# 7-channel-PWM_compact.net
KiCad netlist of a schematic drawn in EAGLE
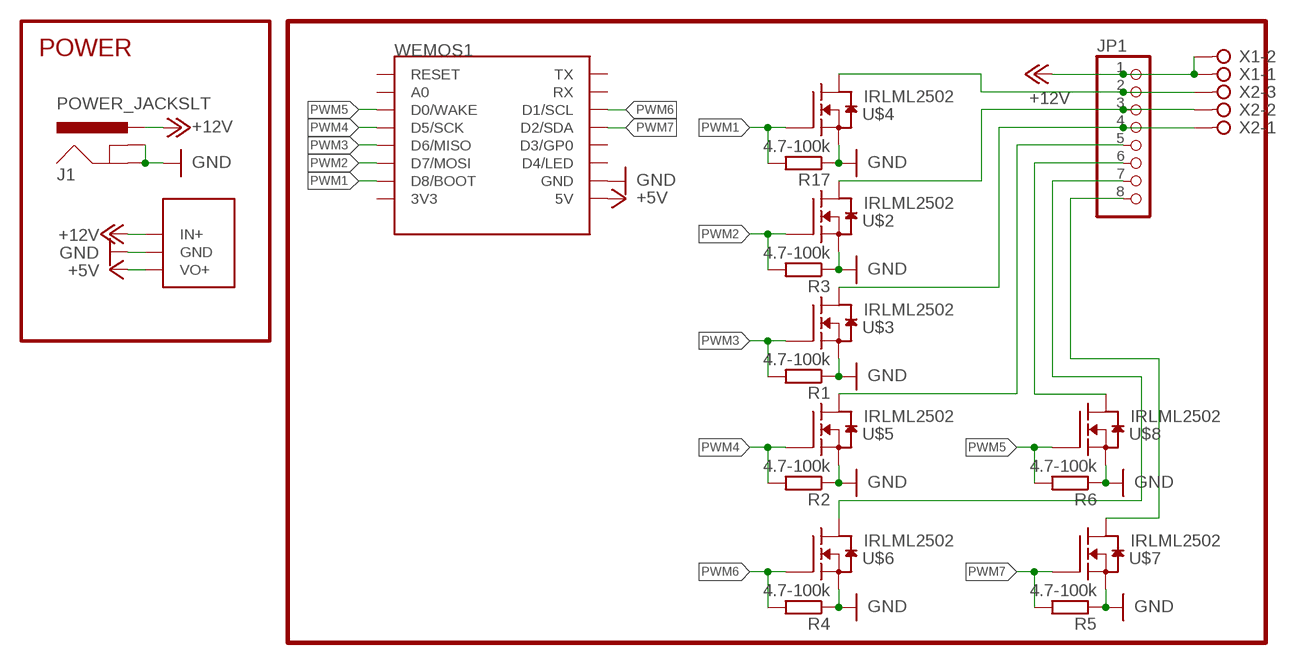
[diagram p0: schematic, sheet 1]

(export (version "E")
  (design (tool "Eeschema 10.0.6"))
  (components
    (comp (ref "J1")
      (value "POWER_JACKSLT")
      (footprint "eagle-import:POWER_JACK_SLOT")
      (libsource (lib "eagle-import") (part "POWER_JACKSLT"))
    )
    (comp (ref "JP1")
      (value "PINHD-1X08_2.54-S")
      (footprint "eagle-import:1X08-S")
      (libsource (lib "eagle-import") (part "PINHD-1X08_2.54-S"))
    )
    (comp (ref "R1")
      (value "4.7-100k")
      (footprint "eagle-import:R0805")
      (libsource (lib "eagle-import") (part "R-EU_R0805"))
    )
    (comp (ref "R2")
      (value "4.7-100k")
      (footprint "eagle-import:R0805")
      (libsource (lib "eagle-import") (part "R-EU_R0805"))
    )
    (comp (ref "R3")
      (value "4.7-100k")
      (footprint "eagle-import:R0805")
      (libsource (lib "eagle-import") (part "R-EU_R0805"))
    )
    (comp (ref "R4")
      (value "4.7-100k")
      (footprint "eagle-import:R0805")
      (libsource (lib "eagle-import") (part "R-EU_R0805"))
    )
    (comp (ref "R5")
      (value "4.7-100k")
      (footprint "eagle-import:R0805")
      (libsource (lib "eagle-import") (part "R-EU_R0805"))
    )
    (comp (ref "R6")
      (value "4.7-100k")
      (footprint "eagle-import:R0805")
      (libsource (lib "eagle-import") (part "R-EU_R0805"))
    )
    (comp (ref "R17")
      (value "4.7-100k")
      (footprint "eagle-import:R0805")
      (libsource (lib "eagle-import") (part "R-EU_R0805"))
    )
    (comp (ref "U$1")
      (value "BUCK_CONVERTER_TE818_VAR")
      (footprint "eagle-import:BUCK_CONVERTER_TE818_VAR")
      (libsource (lib "eagle-import") (part "BUCK_CONVERTER_TE818_VAR"))
    )
    (comp (ref "U$2")
      (value "IRLML2502")
      (footprint "eagle-import:SOT23")
      (libsource (lib "eagle-import") (part "N-CH_IRLML2502"))
    )
    (comp (ref "U$3")
      (value "IRLML2502")
      (footprint "eagle-import:SOT23")
      (libsource (lib "eagle-import") (part "N-CH_IRLML2502"))
    )
    (comp (ref "U$4")
      (value "IRLML2502")
      (footprint "eagle-import:SOT23")
      (libsource (lib "eagle-import") (part "N-CH_IRLML2502"))
    )
    (comp (ref "U$5")
      (value "IRLML2502")
      (footprint "eagle-import:SOT23")
      (libsource (lib "eagle-import") (part "N-CH_IRLML2502"))
    )
    (comp (ref "U$6")
      (value "IRLML2502")
      (footprint "eagle-import:SOT23")
      (libsource (lib "eagle-import") (part "N-CH_IRLML2502"))
    )
    (comp (ref "U$7")
      (value "IRLML2502")
      (footprint "eagle-import:SOT23")
      (libsource (lib "eagle-import") (part "N-CH_IRLML2502"))
    )
    (comp (ref "U$8")
      (value "IRLML2502")
      (footprint "eagle-import:SOT23")
      (libsource (lib "eagle-import") (part "N-CH_IRLML2502"))
    )
    (comp (ref "WEMOS1")
      (value "WEMOS-D1-MINI")
      (footprint "eagle-import:WEMOS-D1-MINI")
      (libsource (lib "eagle-import") (part "WEMOS-D1-MINI"))
    )
    (comp (ref "X1")
      (value "W237-02P")
      (footprint "eagle-import:W237-132")
      (libsource (lib "eagle-import") (part "W237-02P"))
    )
    (comp (ref "X2")
      (value "W237-03P")
      (footprint "eagle-import:W237-133")
      (libsource (lib "eagle-import") (part "W237-03P"))
    )
  )
  (nets
    (net (code "1") (name "+5V") (class "Default")
      (node (ref "U$1") (pin "VO+") (pinfunction "VO+_VO+") (pintype "bidirectional"))
      (node (ref "WEMOS1") (pin "5V") (pinfunction "5V_5V") (pintype "bidirectional"))
    )
    (net (code "2") (name "+12V") (class "Default")
      (node (ref "J1") (pin "PWR") (pinfunction "PWR_PWR") (pintype "bidirectional"))
      (node (ref "JP1") (pin "1") (pinfunction "1_1") (pintype "passive"))
      (node (ref "U$1") (pin "IN+") (pinfunction "IN+_IN+") (pintype "bidirectional"))
      (node (ref "X1") (pin "1") (pinfunction "KL_1") (pintype "passive"))
      (node (ref "X1") (pin "2") (pinfunction "KL_2") (pintype "passive"))
    )
    (net (code "3") (name "GND") (class "Default")
      (node (ref "J1") (pin "GND@1") (pinfunction "GNDBREAK_GND@1") (pintype "bidirectional"))
      (node (ref "J1") (pin "GND@2") (pinfunction "GND_GND@2") (pintype "bidirectional"))
      (node (ref "R1") (pin "1") (pinfunction "1_1") (pintype "passive"))
      (node (ref "R17") (pin "1") (pinfunction "1_1") (pintype "passive"))
      (node (ref "R2") (pin "1") (pinfunction "1_1") (pintype "passive"))
      (node (ref "R3") (pin "1") (pinfunction "1_1") (pintype "passive"))
      (node (ref "R4") (pin "1") (pinfunction "1_1") (pintype "passive"))
      (node (ref "R5") (pin "1") (pinfunction "1_1") (pintype "passive"))
      (node (ref "R6") (pin "1") (pinfunction "1_1") (pintype "passive"))
      (node (ref "U$1") (pin "GND") (pinfunction "GND_GND") (pintype "bidirectional"))
      (node (ref "U$2") (pin "2") (pinfunction "S_2") (pintype "passive"))
      (node (ref "U$3") (pin "2") (pinfunction "S_2") (pintype "passive"))
      (node (ref "U$4") (pin "2") (pinfunction "S_2") (pintype "passive"))
      (node (ref "U$5") (pin "2") (pinfunction "S_2") (pintype "passive"))
      (node (ref "U$6") (pin "2") (pinfunction "S_2") (pintype "passive"))
      (node (ref "U$7") (pin "2") (pinfunction "S_2") (pintype "passive"))
      (node (ref "U$8") (pin "2") (pinfunction "S_2") (pintype "passive"))
      (node (ref "WEMOS1") (pin "GND") (pinfunction "GND_GND") (pintype "bidirectional"))
    )
    (net (code "4") (name "Net-(U$2-D)") (class "Default")
      (node (ref "JP1") (pin "3") (pinfunction "3_3") (pintype "passive"))
      (node (ref "U$2") (pin "3") (pinfunction "D_3") (pintype "passive"))
      (node (ref "X2") (pin "2") (pinfunction "KL_2") (pintype "passive"))
    )
    (net (code "5") (name "Net-(U$3-D)") (class "Default")
      (node (ref "JP1") (pin "4") (pinfunction "4_4") (pintype "passive"))
      (node (ref "U$3") (pin "3") (pinfunction "D_3") (pintype "passive"))
      (node (ref "X2") (pin "1") (pinfunction "KL_1") (pintype "passive"))
    )
    (net (code "6") (name "Net-(U$4-D)") (class "Default")
      (node (ref "JP1") (pin "2") (pinfunction "2_2") (pintype "passive"))
      (node (ref "U$4") (pin "3") (pinfunction "D_3") (pintype "passive"))
      (node (ref "X2") (pin "3") (pinfunction "KL_3") (pintype "passive"))
    )
    (net (code "7") (name "Net-(U$5-D)") (class "Default")
      (node (ref "JP1") (pin "5") (pinfunction "5_5") (pintype "passive"))
      (node (ref "U$5") (pin "3") (pinfunction "D_3") (pintype "passive"))
    )
    (net (code "8") (name "Net-(U$6-D)") (class "Default")
      (node (ref "JP1") (pin "7") (pinfunction "7_7") (pintype "passive"))
      (node (ref "U$6") (pin "3") (pinfunction "D_3") (pintype "passive"))
    )
    (net (code "9") (name "Net-(U$7-D)") (class "Default")
      (node (ref "JP1") (pin "8") (pinfunction "8_8") (pintype "passive"))
      (node (ref "U$7") (pin "3") (pinfunction "D_3") (pintype "passive"))
    )
    (net (code "10") (name "Net-(U$8-D)") (class "Default")
      (node (ref "JP1") (pin "6") (pinfunction "6_6") (pintype "passive"))
      (node (ref "U$8") (pin "3") (pinfunction "D_3") (pintype "passive"))
    )
    (net (code "11") (name "PWM1") (class "Default")
      (node (ref "R17") (pin "2") (pinfunction "2_2") (pintype "passive"))
      (node (ref "U$4") (pin "1") (pinfunction "G_1") (pintype "passive"))
      (node (ref "WEMOS1") (pin "D8") (pinfunction "D8/BOOT_D8") (pintype "bidirectional"))
    )
    (net (code "12") (name "PWM2") (class "Default")
      (node (ref "R3") (pin "2") (pinfunction "2_2") (pintype "passive"))
      (node (ref "U$2") (pin "1") (pinfunction "G_1") (pintype "passive"))
      (node (ref "WEMOS1") (pin "D7") (pinfunction "D7/MOSI_D7") (pintype "bidirectional"))
    )
    (net (code "13") (name "PWM3") (class "Default")
      (node (ref "R1") (pin "2") (pinfunction "2_2") (pintype "passive"))
      (node (ref "U$3") (pin "1") (pinfunction "G_1") (pintype "passive"))
      (node (ref "WEMOS1") (pin "D6") (pinfunction "D6/MISO_D6") (pintype "bidirectional"))
    )
    (net (code "14") (name "PWM4") (class "Default")
      (node (ref "R2") (pin "2") (pinfunction "2_2") (pintype "passive"))
      (node (ref "U$5") (pin "1") (pinfunction "G_1") (pintype "passive"))
      (node (ref "WEMOS1") (pin "D5") (pinfunction "D5/SCK_D5") (pintype "bidirectional"))
    )
    (net (code "15") (name "PWM5") (class "Default")
      (node (ref "R6") (pin "2") (pinfunction "2_2") (pintype "passive"))
      (node (ref "U$8") (pin "1") (pinfunction "G_1") (pintype "passive"))
      (node (ref "WEMOS1") (pin "D0") (pinfunction "D0/WAKE_D0") (pintype "bidirectional"))
    )
    (net (code "16") (name "PWM6") (class "Default")
      (node (ref "R4") (pin "2") (pinfunction "2_2") (pintype "passive"))
      (node (ref "U$6") (pin "1") (pinfunction "G_1") (pintype "passive"))
      (node (ref "WEMOS1") (pin "D1") (pinfunction "D1/SCL_D1") (pintype "bidirectional"))
    )
    (net (code "17") (name "PWM7") (class "Default")
      (node (ref "R5") (pin "2") (pinfunction "2_2") (pintype "passive"))
      (node (ref "U$7") (pin "1") (pinfunction "G_1") (pintype "passive"))
      (node (ref "WEMOS1") (pin "D2") (pinfunction "D2/SDA_D2") (pintype "bidirectional"))
    )
    (net (code "18") (name "unconnected-(WEMOS1-D3{slash}GP0-PadD3)") (class "Default")
      (node (ref "WEMOS1") (pin "D3") (pinfunction "D3/GP0_D3") (pintype "bidirectional"))
    )
    (net (code "19") (name "unconnected-(WEMOS1-D4{slash}LED-PadD4)") (class "Default")
      (node (ref "WEMOS1") (pin "D4") (pinfunction "D4/LED_D4") (pintype "bidirectional"))
    )
    (net (code "20") (name "unconnected-(WEMOS1-Pad3V3)") (class "Default")
      (node (ref "WEMOS1") (pin "3V3") (pinfunction "3V3_3V3") (pintype "bidirectional"))
    )
    (net (code "21") (name "unconnected-(WEMOS1-PadA0)") (class "Default")
      (node (ref "WEMOS1") (pin "A0") (pinfunction "A0_A0") (pintype "bidirectional"))
    )
    (net (code "22") (name "unconnected-(WEMOS1-PadRESET)") (class "Default")
      (node (ref "WEMOS1") (pin "RESET") (pinfunction "RESET_RESET") (pintype "bidirectional"))
    )
    (net (code "23") (name "unconnected-(WEMOS1-PadRX)") (class "Default")
      (node (ref "WEMOS1") (pin "RX") (pinfunction "RX_RX") (pintype "bidirectional"))
    )
    (net (code "24") (name "unconnected-(WEMOS1-PadTX)") (class "Default")
      (node (ref "WEMOS1") (pin "TX") (pinfunction "TX_TX") (pintype "bidirectional"))
    )
  )
)
